# Power_Supply.net
KiCad netlist of a schematic drawn in Altium Designer
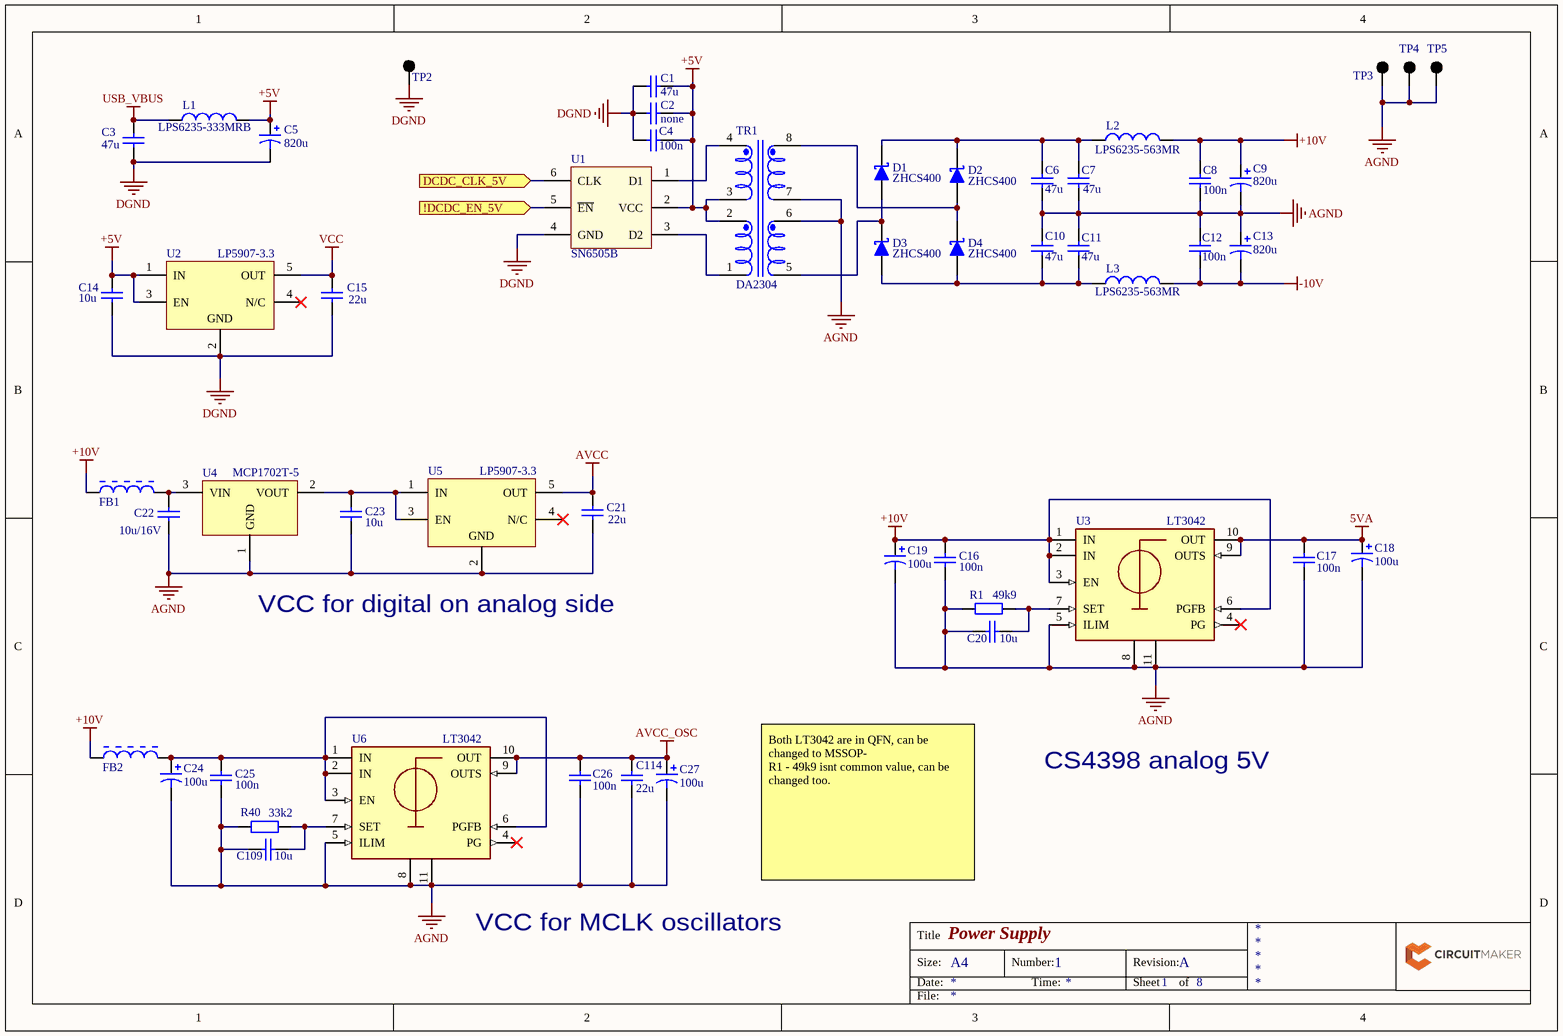
[diagram p0: Power_Supply.SchDoc]

(export (version "E")
  (design (tool "Eeschema 10.0.6"))
  (components
    (comp (ref "C1")
      (value "47u")
      (footprint "PCB-6alau6k4isvsg1wxu4va-1")
      (description "1210 100 uF 16 V ±20% Tolerance X5R SMT Multilayer Ceramic Capacitor")
      (libsource (lib "CommunityVault") (part "CMP-a2006a3718e57dc7-1"))
    )
    (comp (ref "C2")
      (value "none")
      (footprint "PCB-6alau6k4isvsg1wxu4va-1")
      (description "1210 100 uF 16 V ±20% Tolerance X5R SMT Multilayer Ceramic Capacitor")
      (libsource (lib "CommunityVault") (part "SYM-a2006a3718e57dc7-1"))
    )
    (comp (ref "C3")
      (value "47u")
      (footprint "PCB-6alau6k4isvsg1wxu4va-1")
      (description "1210 100 uF 16 V ±20% Tolerance X5R SMT Multilayer Ceramic Capacitor")
      (libsource (lib "CommunityVault") (part "SYM-a2006a3718e57dc7-1"))
    )
    (comp (ref "C4")
      (value "100n")
      (footprint "PCB-rf0pzaa82dpbeu9l4sxm-1")
      (description "Generic Capacitor 0603")
      (fields (field (name "LCSC PART #") "C14663"))
      (libsource (lib "FavoritesLibrary") (part "SYM-x8hddryxw4o380xfi98v-1"))
    )
    (comp (ref "C5")
      (value "820u")
      (footprint "A750MS827M1CAAE013")
      (description "Cap Aluminum Polymer 1000uF 16VDC 20% (10 X 12mm) Radial 5mm 0.013 Ohm 5250mA 2000h 105C Bag")
      (libsource (lib "CommunityVault") (part "SYM-1544d833d83eca83-1"))
    )
    (comp (ref "C6")
      (value "47u")
      (footprint "PCB-6alau6k4isvsg1wxu4va-1")
      (description "1210 100 uF 16 V ±20% Tolerance X5R SMT Multilayer Ceramic Capacitor")
      (libsource (lib "CommunityVault") (part "CMP-a2006a3718e57dc7-1"))
    )
    (comp (ref "C7")
      (value "47u")
      (footprint "PCB-6alau6k4isvsg1wxu4va-1")
      (description "1210 100 uF 16 V ±20% Tolerance X5R SMT Multilayer Ceramic Capacitor")
      (libsource (lib "CommunityVault") (part "SYM-a2006a3718e57dc7-1"))
    )
    (comp (ref "C8")
      (value "100n")
      (footprint "PCB-rf0pzaa82dpbeu9l4sxm-1")
      (description "Generic Capacitor 0603")
      (fields (field (name "LCSC PART #") "C14663"))
      (libsource (lib "FavoritesLibrary") (part "SYM-x8hddryxw4o380xfi98v-1"))
    )
    (comp (ref "C9")
      (value "820u")
      (footprint "A750MS827M1CAAE013")
      (description "Cap Aluminum Polymer 1000uF 16VDC 20% (10 X 12mm) Radial 5mm 0.013 Ohm 5250mA 2000h 105C Bag")
      (libsource (lib "CommunityVault") (part "SYM-1544d833d83eca83-1"))
    )
    (comp (ref "C10")
      (value "47u")
      (footprint "PCB-6alau6k4isvsg1wxu4va-1")
      (description "1210 100 uF 16 V ±20% Tolerance X5R SMT Multilayer Ceramic Capacitor")
      (libsource (lib "CommunityVault") (part "SYM-a2006a3718e57dc7-1"))
    )
    (comp (ref "C11")
      (value "47u")
      (footprint "PCB-6alau6k4isvsg1wxu4va-1")
      (description "1210 100 uF 16 V ±20% Tolerance X5R SMT Multilayer Ceramic Capacitor")
      (libsource (lib "CommunityVault") (part "SYM-a2006a3718e57dc7-1"))
    )
    (comp (ref "C12")
      (value "100n")
      (footprint "PCB-rf0pzaa82dpbeu9l4sxm-1")
      (description "Generic Capacitor 0603")
      (fields (field (name "LCSC PART #") "C14663"))
      (libsource (lib "FavoritesLibrary") (part "SYM-x8hddryxw4o380xfi98v-1"))
    )
    (comp (ref "C13")
      (value "820u")
      (footprint "A750MS827M1CAAE013")
      (description "Cap Aluminum Polymer 1000uF 16VDC 20% (10 X 12mm) Radial 5mm 0.013 Ohm 5250mA 2000h 105C Bag")
      (libsource (lib "CommunityVault") (part "SYM-1544d833d83eca83-1"))
    )
    (comp (ref "C14")
      (value "10u")
      (footprint "PCB-rf0pzaa82dpbeu9l4sxm-1")
      (description "Capacitor 0603")
      (fields (field (name "LCSC PART #") "C19702") (field (name "LCSC PART #_1") "C25804"))
      (libsource (lib "FavoritesLibrary") (part "SYM-x8hddryxw4o380xfi98v-1"))
    )
    (comp (ref "C15")
      (value "22u")
      (footprint "PCB-rf0pzaa82dpbeu9l4sxm-1")
      (description "Capacitor 0603")
      (fields (field (name "LCSC PART #") "C59461"))
      (libsource (lib "FavoritesLibrary") (part "SYM-x8hddryxw4o380xfi98v-1"))
    )
    (comp (ref "C16")
      (value "100n")
      (footprint "PCB-rf0pzaa82dpbeu9l4sxm-1")
      (description "Capacitor 0603")
      (fields (field (name "LCSC PART #") "C14663"))
      (libsource (lib "FavoritesLibrary") (part "SYM-x8hddryxw4o380xfi98v-1"))
    )
    (comp (ref "C17")
      (value "100n")
      (footprint "PCB-rf0pzaa82dpbeu9l4sxm-1")
      (description "Capacitor 0603")
      (fields (field (name "LCSC PART #") "C14663"))
      (libsource (lib "FavoritesLibrary") (part "SYM-x8hddryxw4o380xfi98v-1"))
    )
    (comp (ref "C18")
      (value "100u")
      (footprint "PCB-9bfrndi9huxo1n7cihpl-1")
      (description "In a Pack of 25, KEMET 100?F Electrolytic Capacitor 10V dc Through Hole - A758EK107M1AAAE016")
      (fields (field (name "MANUFACTURER PART NUMBER") "A758EK107M1AAAE016"))
      (libsource (lib "FavoritesLibrary") (part "SYM-6546a831a81eba81-3"))
    )
    (comp (ref "C19")
      (value "100u")
      (footprint "PCB-9bfrndi9huxo1n7cihpl-1")
      (description "In a Pack of 25, KEMET 100?F Electrolytic Capacitor 10V dc Through Hole - A758EK107M1AAAE016")
      (fields (field (name "MANUFACTURER PART NUMBER") "A758EK107M1AAAE016"))
      (libsource (lib "FavoritesLibrary") (part "SYM-6546a831a81eba81-3"))
    )
    (comp (ref "C20")
      (value "10u")
      (footprint "PCB-rf0pzaa82dpbeu9l4sxm-1")
      (description "Capacitor 0603")
      (fields (field (name "LCSC PART #") "C19702"))
      (libsource (lib "FavoritesLibrary") (part "SYM-x8hddryxw4o380xfi98v-1"))
    )
    (comp (ref "C21")
      (value "22u")
      (footprint "PCB-rf0pzaa82dpbeu9l4sxm-1")
      (description "Capacitor 0603")
      (fields (field (name "LCSC PART #") "C59461"))
      (libsource (lib "FavoritesLibrary") (part "SYM-x8hddryxw4o380xfi98v-1"))
    )
    (comp (ref "C22")
      (value "10u/16V")
      (footprint "PCB-rf0pzaa82dpbeu9l4sxm-1")
      (description "Capacitor 0603")
      (libsource (lib "FavoritesLibrary") (part "SYM-x8hddryxw4o380xfi98v-1"))
    )
    (comp (ref "C23")
      (value "10u")
      (footprint "PCB-rf0pzaa82dpbeu9l4sxm-1")
      (description "Capacitor 0603")
      (fields (field (name "LCSC PART #") "C19702"))
      (libsource (lib "FavoritesLibrary") (part "SYM-x8hddryxw4o380xfi98v-1"))
    )
    (comp (ref "C24")
      (value "100u")
      (footprint "PCB-9bfrndi9huxo1n7cihpl-1")
      (description "In a Pack of 25, KEMET 100?F Electrolytic Capacitor 10V dc Through Hole - A758EK107M1AAAE016")
      (fields (field (name "MANUFACTURER PART NUMBER") "A758EK107M1AAAE016"))
      (libsource (lib "FavoritesLibrary") (part "SYM-6546a831a81eba81-3"))
    )
    (comp (ref "C25")
      (value "100n")
      (footprint "PCB-rf0pzaa82dpbeu9l4sxm-1")
      (description "Capacitor 0603")
      (fields (field (name "LCSC PART #") "C14663"))
      (libsource (lib "FavoritesLibrary") (part "SYM-x8hddryxw4o380xfi98v-1"))
    )
    (comp (ref "C26")
      (value "100n")
      (footprint "PCB-rf0pzaa82dpbeu9l4sxm-1")
      (description "Capacitor 0603")
      (fields (field (name "LCSC PART #") "C14663"))
      (libsource (lib "FavoritesLibrary") (part "SYM-x8hddryxw4o380xfi98v-1"))
    )
    (comp (ref "C27")
      (value "100u")
      (footprint "PCB-9bfrndi9huxo1n7cihpl-1")
      (description "In a Pack of 25, KEMET 100?F Electrolytic Capacitor 10V dc Through Hole - A758EK107M1AAAE016")
      (fields (field (name "MANUFACTURER PART NUMBER") "A758EK107M1AAAE016"))
      (libsource (lib "FavoritesLibrary") (part "SYM-6546a831a81eba81-3"))
    )
    (comp (ref "C109")
      (value "10u")
      (footprint "PCB-rf0pzaa82dpbeu9l4sxm-1")
      (description "Capacitor 0603")
      (fields (field (name "LCSC PART #") "C19702"))
      (libsource (lib "FavoritesLibrary") (part "SYM-x8hddryxw4o380xfi98v-1"))
    )
    (comp (ref "C114")
      (value "22u")
      (footprint "PCB-rf0pzaa82dpbeu9l4sxm-1")
      (description "Capacitor 0603")
      (fields (field (name "LCSC PART #") "C59461"))
      (libsource (lib "FavoritesLibrary") (part "SYM-x8hddryxw4o380xfi98v-1"))
    )
    (comp (ref "D1")
      (value "ZHCS400")
      (footprint "PCB-mrclmtn06znaca5ywvvw-1")
      (description "Schottky Rectifier, 0.4A, 40V SOD-323")
      (libsource (lib "CommunityVault") (part "CMP-3796931-5"))
    )
    (comp (ref "D2")
      (value "ZHCS400")
      (footprint "PCB-mrclmtn06znaca5ywvvw-1")
      (description "Schottky Rectifier, 0.4A, 40V SOD-323")
      (libsource (lib "CommunityVault") (part "SYM-21c3e801b532fe04-1"))
    )
    (comp (ref "D3")
      (value "ZHCS400")
      (footprint "PCB-mrclmtn06znaca5ywvvw-1")
      (description "Schottky Rectifier, 0.4A, 40V SOD-323")
      (libsource (lib "CommunityVault") (part "SYM-21c3e801b532fe04-1"))
    )
    (comp (ref "D4")
      (value "ZHCS400")
      (footprint "PCB-mrclmtn06znaca5ywvvw-1")
      (description "Schottky Rectifier, 0.4A, 40V SOD-323")
      (libsource (lib "CommunityVault") (part "SYM-21c3e801b532fe04-1"))
    )
    (comp (ref "FB1")
      (value "BLM18EG391TN1D")
      (footprint "MURA-BLM18-F-H3-CHIP-2_V")
      (libsource (lib "CommunityVault") (part "MURA-FB-2"))
    )
    (comp (ref "FB2")
      (value "BLM18EG391TN1D")
      (footprint "MURA-BLM18-F-H3-CHIP-2_V")
      (libsource (lib "CommunityVault") (part "MURA-FB-2"))
    )
    (comp (ref "L1")
      (value "LPS6235-333MRB")
      (footprint "LPS6235")
      (description "Power inductor, shielded, 20% tol, SMT, RoHS, lead-free, halogen-free")
      (libsource (lib "CommunityVault") (part "SYM-f5873d4763982a40-1"))
    )
    (comp (ref "L2")
      (value "LPS6235-563MR")
      (footprint "PCB-91apuy3syfgd6vk6qbo6-1")
      (description "Power inductor, shielded, 20% tol, SMT, RoHS, lead-free, halogen-free")
      (libsource (lib "CommunityVault") (part "SYM-db2813e84dcb04ef-1"))
    )
    (comp (ref "L3")
      (value "LPS6235-563MR")
      (footprint "PCB-91apuy3syfgd6vk6qbo6-1")
      (description "Power inductor, shielded, 20% tol, SMT, RoHS, lead-free, halogen-free")
      (libsource (lib "CommunityVault") (part "SYM-db2813e84dcb04ef-1"))
    )
    (comp (ref "R1")
      (value "49k9")
      (footprint "PCB-3d5y3t7f8drf35yjcj59-1")
      (description "Resistor 0603")
      (libsource (lib "FavoritesLibrary") (part "SYM-xcu3s4ikiffkkgbeyow5-1"))
    )
    (comp (ref "R40")
      (value "33k2")
      (footprint "PCB-3d5y3t7f8drf35yjcj59-1")
      (description "Resistor 0603")
      (libsource (lib "FavoritesLibrary") (part "SYM-xcu3s4ikiffkkgbeyow5-1"))
    )
    (comp (ref "TP2")
      (value "Keystone Electronics 5001")
      (footprint "P1-09")
      (description "KEYSTONE   5001   TEST POINT, PCB, THROUGH HOLE")
      (libsource (lib "FavoritesLibrary") (part "KSTN-5001"))
    )
    (comp (ref "TP3")
      (value "Keystone Electronics 5001")
      (footprint "P1-09")
      (description "KEYSTONE   5001   TEST POINT, PCB, THROUGH HOLE")
      (libsource (lib "FavoritesLibrary") (part "KSTN-5001"))
    )
    (comp (ref "TP4")
      (value "Keystone Electronics 5001")
      (footprint "P1-09")
      (description "KEYSTONE   5001   TEST POINT, PCB, THROUGH HOLE")
      (libsource (lib "FavoritesLibrary") (part "KSTN-5001"))
    )
    (comp (ref "TP5")
      (value "Keystone Electronics 5001")
      (footprint "P1-09")
      (description "KEYSTONE   5001   TEST POINT, PCB, THROUGH HOLE")
      (libsource (lib "FavoritesLibrary") (part "KSTN-5001"))
    )
    (comp (ref "TR1")
      (value "DA2304")
      (footprint "PCB-wryx25zm61bkpund2vng-1")
      (description "Transformer, for ADM2485, 5-6V, SMT, RoHS")
      (fields (field (name "MANUFACTURER PART NUMBER") "DA2303-ALB"))
      (libsource (lib "CommunityVault") (part "CMP-7cc7b5ab862da300-5"))
    )
    (comp (ref "U1")
      (value "SN6505B")
      (footprint "PCB-z49b8x4xdp07datjgpqp-1")
      (description "Low-Noise 1 A, 420 kHz Transformer Driver 6-SOT-23 -55 to 125")
      (fields (field (name "MANUFACTURER PART NUMBER") "SN6505BDBVT"))
      (libsource (lib "CommunityVault") (part "CMP-a28c686de0427d4b-3"))
    )
    (comp (ref "U2")
      (value "LP5907-3.3")
      (footprint "PCB-ab03it339uw922kmt1cl-1")
      (description "250mA Ultralow-Noise Low-IQ LDO 4-DSBGA -40 to 125")
      (fields (field (name "MANUFACTURER PART NUMBER") "LP5907UVX-3.3/NOPB"))
      (libsource (lib "FavoritesLibrary") (part "SYM-9de05591815b4227-1"))
    )
    (comp (ref "U3")
      (value "LT3042")
      (footprint "PCB-n2zh5wqg9qgt346qmob6-1")
      (description "LT3042 - 20V, 200mA, Ultralow Noise, Ultrahigh PSRR RF Linear Regulator")
      (fields (field (name "MANUFACTURER PART NUMBER") "LT3042EDD#PBF"))
      (libsource (lib "CommunityVault") (part "SYM-ff8235e0d3752045-1"))
    )
    (comp (ref "U4")
      (value "MCP1702T-5")
      (footprint "SOT-23A-CB3_L")
      (description "250 mA Low Quiescent Current LDO Regulator, 3-Pin SOT-23A, Extended Temperature, Tape and Reel")
      (fields (field (name "MANUFACTURER PART NUMBER") "MCP1702T-5002E/CB"))
      (libsource (lib "FavoritesLibrary") (part "PM-LINEREG-MCP1702-IL3"))
    )
    (comp (ref "U5")
      (value "LP5907-3.3")
      (footprint "PCB-ab03it339uw922kmt1cl-1")
      (description "250mA Ultralow-Noise Low-IQ LDO 4-DSBGA -40 to 125")
      (fields (field (name "MANUFACTURER PART NUMBER") "LP5907UVX-3.3/NOPB"))
      (libsource (lib "FavoritesLibrary") (part "SYM-9de05591815b4227-1"))
    )
    (comp (ref "U6")
      (value "LT3042")
      (footprint "PCB-n2zh5wqg9qgt346qmob6-1")
      (description "LT3042 - 20V, 200mA, Ultralow Noise, Ultrahigh PSRR RF Linear Regulator")
      (fields (field (name "MANUFACTURER PART NUMBER") "LT3042EDD#PBF"))
      (libsource (lib "CommunityVault") (part "SYM-ff8235e0d3752045-1"))
    )
  )
  (nets
    (net (code "1") (name "+5V") (class "Default")
      (node (ref "C1") (pin "1") (pinfunction "1_1") (pintype "passive"))
      (node (ref "C14") (pin "2") (pinfunction "2_2") (pintype "passive"))
      (node (ref "C2") (pin "1") (pinfunction "1_1") (pintype "passive"))
      (node (ref "C4") (pin "2") (pinfunction "2_2") (pintype "passive"))
      (node (ref "C5") (pin "1") (pinfunction "1_1") (pintype "passive"))
      (node (ref "L1") (pin "2") (pinfunction "2_2") (pintype "passive"))
      (node (ref "TR1") (pin "2") (pinfunction "2_2") (pintype "passive"))
      (node (ref "TR1") (pin "3") (pinfunction "3_3") (pintype "passive"))
      (node (ref "U1") (pin "2") (pinfunction "VCC_2") (pintype "passive"))
      (node (ref "U2") (pin "1") (pinfunction "IN_1") (pintype "power_in"))
      (node (ref "U2") (pin "3") (pinfunction "EN_3") (pintype "passive"))
    )
    (net (code "2") (name "+10V") (class "Default")
      (node (ref "C16") (pin "2") (pinfunction "2_2") (pintype "passive"))
      (node (ref "C19") (pin "1") (pinfunction "1_1") (pintype "passive"))
      (node (ref "C8") (pin "2") (pinfunction "2_2") (pintype "passive"))
      (node (ref "C9") (pin "1") (pinfunction "1_1") (pintype "passive"))
      (node (ref "FB1") (pin "1") (pinfunction "1_1") (pintype "passive"))
      (node (ref "FB2") (pin "1") (pinfunction "1_1") (pintype "passive"))
      (node (ref "L2") (pin "2") (pinfunction "2_2") (pintype "passive"))
      (node (ref "U3") (pin "1") (pinfunction "IN_1") (pintype "power_in"))
      (node (ref "U3") (pin "2") (pinfunction "IN_2") (pintype "power_in"))
      (node (ref "U3") (pin "3") (pinfunction "EN_3") (pintype "input"))
      (node (ref "U3") (pin "6") (pinfunction "PGFB_6") (pintype "input"))
    )
    (net (code "3") (name "-10V") (class "Default")
      (node (ref "C12") (pin "1") (pinfunction "1_1") (pintype "passive"))
      (node (ref "C13") (pin "2") (pinfunction "2_2") (pintype "passive"))
      (node (ref "L3") (pin "2") (pinfunction "2_2") (pintype "passive"))
    )
    (net (code "4") (name "/!DCDC_EN_5V") (class "Default")
      (node (ref "U1") (pin "5") (pinfunction "~{EN}_5") (pintype "passive"))
    )
    (net (code "5") (name "/DCDC_CLK_5V") (class "Default")
      (node (ref "U1") (pin "6") (pinfunction "CLK_6") (pintype "passive"))
    )
    (net (code "6") (name "5VA") (class "Default")
      (node (ref "C17") (pin "2") (pinfunction "2_2") (pintype "passive"))
      (node (ref "C18") (pin "1") (pinfunction "1_1") (pintype "passive"))
      (node (ref "U3") (pin "10") (pinfunction "OUT_10") (pintype "power_in"))
      (node (ref "U3") (pin "9") (pinfunction "OUTS_9") (pintype "input"))
    )
    (net (code "7") (name "AGND") (class "Default")
      (node (ref "C10") (pin "2") (pinfunction "2_2") (pintype "passive"))
      (node (ref "C109") (pin "2") (pinfunction "2_2") (pintype "passive"))
      (node (ref "C11") (pin "2") (pinfunction "2_2") (pintype "passive"))
      (node (ref "C114") (pin "1") (pinfunction "1_1") (pintype "passive"))
      (node (ref "C12") (pin "2") (pinfunction "2_2") (pintype "passive"))
      (node (ref "C13") (pin "1") (pinfunction "1_1") (pintype "passive"))
      (node (ref "C16") (pin "1") (pinfunction "1_1") (pintype "passive"))
      (node (ref "C17") (pin "1") (pinfunction "1_1") (pintype "passive"))
      (node (ref "C18") (pin "2") (pinfunction "2_2") (pintype "passive"))
      (node (ref "C19") (pin "2") (pinfunction "2_2") (pintype "passive"))
      (node (ref "C20") (pin "2") (pinfunction "2_2") (pintype "passive"))
      (node (ref "C21") (pin "1") (pinfunction "1_1") (pintype "passive"))
      (node (ref "C22") (pin "1") (pinfunction "1_1") (pintype "passive"))
      (node (ref "C23") (pin "1") (pinfunction "1_1") (pintype "passive"))
      (node (ref "C24") (pin "2") (pinfunction "2_2") (pintype "passive"))
      (node (ref "C25") (pin "1") (pinfunction "1_1") (pintype "passive"))
      (node (ref "C26") (pin "1") (pinfunction "1_1") (pintype "passive"))
      (node (ref "C27") (pin "2") (pinfunction "2_2") (pintype "passive"))
      (node (ref "C6") (pin "1") (pinfunction "1_1") (pintype "passive"))
      (node (ref "C7") (pin "1") (pinfunction "1_1") (pintype "passive"))
      (node (ref "C8") (pin "1") (pinfunction "1_1") (pintype "passive"))
      (node (ref "C9") (pin "2") (pinfunction "2_2") (pintype "passive"))
      (node (ref "R1") (pin "2") (pinfunction "2_2") (pintype "passive"))
      (node (ref "R40") (pin "2") (pinfunction "2_2") (pintype "passive"))
      (node (ref "TP3") (pin "1") (pinfunction "1_1") (pintype "passive"))
      (node (ref "TP4") (pin "1") (pinfunction "1_1") (pintype "passive"))
      (node (ref "TP5") (pin "1") (pinfunction "1_1") (pintype "passive"))
      (node (ref "TR1") (pin "6") (pinfunction "6_6") (pintype "passive"))
      (node (ref "TR1") (pin "7") (pinfunction "7_7") (pintype "passive"))
      (node (ref "U3") (pin "11") (pinfunction "GND_11") (pintype "power_in"))
      (node (ref "U3") (pin "5") (pinfunction "ILIM_5") (pintype "input"))
      (node (ref "U3") (pin "8") (pinfunction "GND_8") (pintype "power_in"))
      (node (ref "U4") (pin "1") (pinfunction "GND_1") (pintype "passive"))
      (node (ref "U5") (pin "2") (pinfunction "GND_2") (pintype "power_in"))
      (node (ref "U6") (pin "11") (pinfunction "GND_11") (pintype "power_in"))
      (node (ref "U6") (pin "5") (pinfunction "ILIM_5") (pintype "input"))
      (node (ref "U6") (pin "8") (pinfunction "GND_8") (pintype "power_in"))
    )
    (net (code "8") (name "AVCC") (class "Default")
      (node (ref "C21") (pin "2") (pinfunction "2_2") (pintype "passive"))
      (node (ref "U5") (pin "5") (pinfunction "OUT_5") (pintype "power_in"))
    )
    (net (code "9") (name "AVCC_OSC") (class "Default")
      (node (ref "C114") (pin "2") (pinfunction "2_2") (pintype "passive"))
      (node (ref "C26") (pin "2") (pinfunction "2_2") (pintype "passive"))
      (node (ref "C27") (pin "1") (pinfunction "1_1") (pintype "passive"))
      (node (ref "U6") (pin "10") (pinfunction "OUT_10") (pintype "power_in"))
      (node (ref "U6") (pin "9") (pinfunction "OUTS_9") (pintype "input"))
    )
    (net (code "10") (name "DGND") (class "Default")
      (node (ref "C1") (pin "2") (pinfunction "2_2") (pintype "passive"))
      (node (ref "C14") (pin "1") (pinfunction "1_1") (pintype "passive"))
      (node (ref "C15") (pin "1") (pinfunction "1_1") (pintype "passive"))
      (node (ref "C2") (pin "2") (pinfunction "2_2") (pintype "passive"))
      (node (ref "C3") (pin "1") (pinfunction "1_1") (pintype "passive"))
      (node (ref "C4") (pin "1") (pinfunction "1_1") (pintype "passive"))
      (node (ref "C5") (pin "2") (pinfunction "2_2") (pintype "passive"))
      (node (ref "TP2") (pin "1") (pinfunction "1_1") (pintype "passive"))
      (node (ref "U1") (pin "4") (pinfunction "GND_4") (pintype "passive"))
      (node (ref "U2") (pin "2") (pinfunction "GND_2") (pintype "power_in"))
    )
    (net (code "11") (name "Net-(D1-A)") (class "Default")
      (node (ref "D1") (pin "1") (pinfunction "A_1") (pintype "passive"))
      (node (ref "D3") (pin "2") (pinfunction "K_2") (pintype "passive"))
      (node (ref "TR1") (pin "5") (pinfunction "5_5") (pintype "passive"))
    )
    (net (code "12") (name "Net-(D1-K)") (class "Default")
      (node (ref "C6") (pin "2") (pinfunction "2_2") (pintype "passive"))
      (node (ref "C7") (pin "2") (pinfunction "2_2") (pintype "passive"))
      (node (ref "D1") (pin "2") (pinfunction "K_2") (pintype "passive"))
      (node (ref "D2") (pin "2") (pinfunction "K_2") (pintype "passive"))
      (node (ref "L2") (pin "1") (pinfunction "1_1") (pintype "passive"))
    )
    (net (code "13") (name "Net-(D2-A)") (class "Default")
      (node (ref "D2") (pin "1") (pinfunction "A_1") (pintype "passive"))
      (node (ref "D4") (pin "2") (pinfunction "K_2") (pintype "passive"))
      (node (ref "TR1") (pin "8") (pinfunction "8_8") (pintype "passive"))
    )
    (net (code "14") (name "Net-(D3-A)") (class "Default")
      (node (ref "C10") (pin "1") (pinfunction "1_1") (pintype "passive"))
      (node (ref "C11") (pin "1") (pinfunction "1_1") (pintype "passive"))
      (node (ref "D3") (pin "1") (pinfunction "A_1") (pintype "passive"))
      (node (ref "D4") (pin "1") (pinfunction "A_1") (pintype "passive"))
      (node (ref "L3") (pin "1") (pinfunction "1_1") (pintype "passive"))
    )
    (net (code "15") (name "Net-(U1-D1)") (class "Default")
      (node (ref "TR1") (pin "4") (pinfunction "4_4") (pintype "passive"))
      (node (ref "U1") (pin "1") (pinfunction "D1_1") (pintype "passive"))
    )
    (net (code "16") (name "Net-(U1-D2)") (class "Default")
      (node (ref "TR1") (pin "1") (pinfunction "1_1") (pintype "passive"))
      (node (ref "U1") (pin "3") (pinfunction "D2_3") (pintype "passive"))
    )
    (net (code "17") (name "Net-(U3-SET)") (class "Default")
      (node (ref "C20") (pin "1") (pinfunction "1_1") (pintype "passive"))
      (node (ref "R1") (pin "1") (pinfunction "1_1") (pintype "passive"))
      (node (ref "U3") (pin "7") (pinfunction "SET_7") (pintype "input"))
    )
    (net (code "18") (name "Net-(U4-VIN)") (class "Default")
      (node (ref "C22") (pin "2") (pinfunction "2_2") (pintype "passive"))
      (node (ref "FB1") (pin "2") (pinfunction "2_2") (pintype "passive"))
      (node (ref "U4") (pin "3") (pinfunction "VIN_3") (pintype "power_in"))
    )
    (net (code "19") (name "Net-(U4-VOUT)") (class "Default")
      (node (ref "C23") (pin "2") (pinfunction "2_2") (pintype "passive"))
      (node (ref "U4") (pin "2") (pinfunction "VOUT_2") (pintype "power_in"))
      (node (ref "U5") (pin "1") (pinfunction "IN_1") (pintype "power_in"))
      (node (ref "U5") (pin "3") (pinfunction "EN_3") (pintype "passive"))
    )
    (net (code "20") (name "Net-(U6-EN)") (class "Default")
      (node (ref "C24") (pin "1") (pinfunction "1_1") (pintype "passive"))
      (node (ref "C25") (pin "2") (pinfunction "2_2") (pintype "passive"))
      (node (ref "FB2") (pin "2") (pinfunction "2_2") (pintype "passive"))
      (node (ref "U6") (pin "1") (pinfunction "IN_1") (pintype "power_in"))
      (node (ref "U6") (pin "2") (pinfunction "IN_2") (pintype "power_in"))
      (node (ref "U6") (pin "3") (pinfunction "EN_3") (pintype "input"))
      (node (ref "U6") (pin "6") (pinfunction "PGFB_6") (pintype "input"))
    )
    (net (code "21") (name "Net-(U6-SET)") (class "Default")
      (node (ref "C109") (pin "1") (pinfunction "1_1") (pintype "passive"))
      (node (ref "R40") (pin "1") (pinfunction "1_1") (pintype "passive"))
      (node (ref "U6") (pin "7") (pinfunction "SET_7") (pintype "input"))
    )
    (net (code "22") (name "USB_VBUS") (class "Default")
      (node (ref "C3") (pin "2") (pinfunction "2_2") (pintype "passive"))
      (node (ref "L1") (pin "1") (pinfunction "1_1") (pintype "passive"))
    )
    (net (code "23") (name "VCC") (class "Default")
      (node (ref "C15") (pin "2") (pinfunction "2_2") (pintype "passive"))
      (node (ref "U2") (pin "5") (pinfunction "OUT_5") (pintype "power_in"))
    )
    (net (code "24") (name "unconnected-(U2-N{slash}C-Pad4)") (class "Default")
      (node (ref "U2") (pin "4") (pinfunction "N/C_4") (pintype "power_in+no_connect"))
    )
    (net (code "25") (name "unconnected-(U3-PG-Pad4)") (class "Default")
      (node (ref "U3") (pin "4") (pinfunction "PG_4") (pintype "output+no_connect"))
    )
    (net (code "26") (name "unconnected-(U5-N{slash}C-Pad4)") (class "Default")
      (node (ref "U5") (pin "4") (pinfunction "N/C_4") (pintype "power_in+no_connect"))
    )
    (net (code "27") (name "unconnected-(U6-PG-Pad4)") (class "Default")
      (node (ref "U6") (pin "4") (pinfunction "PG_4") (pintype "output+no_connect"))
    )
  )
)
